# micro_schematic.net
KiCad netlist of a schematic drawn in Altium Designer
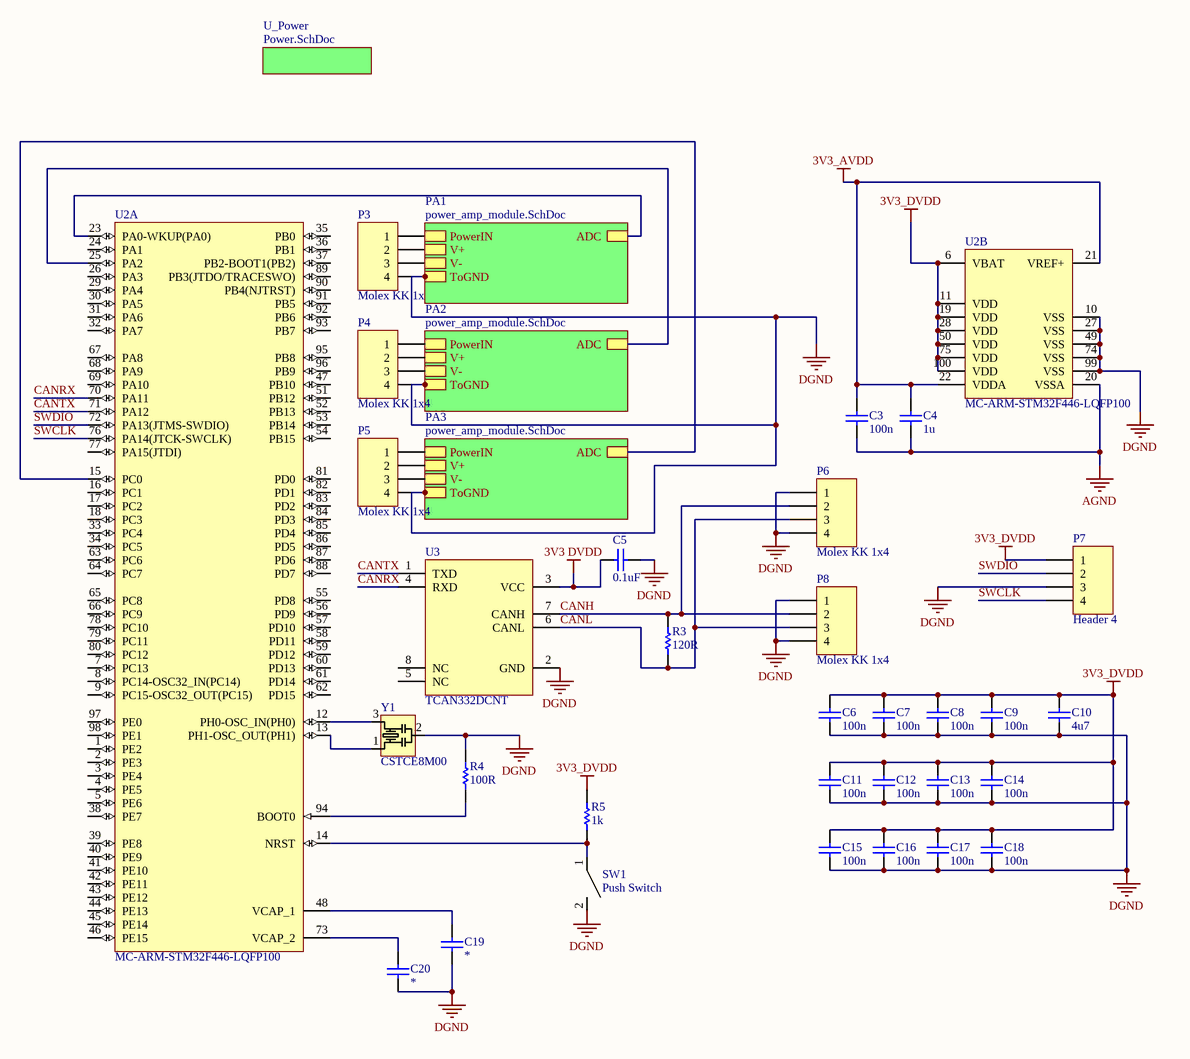
[diagram p0: micro_schematic.SchDoc]

(export (version "E")
  (design (tool "Eeschema 10.0.6"))
  (components
    (comp (ref "C3")
      (value "100n")
      (footprint "C0805")
      (description "0805 Capacitor")
      (libsource (lib "PARSEC") (part "C0805"))
    )
    (comp (ref "C4")
      (value "1u")
      (footprint "C0805")
      (description "0805 Capacitor")
      (libsource (lib "PARSEC") (part "C0805"))
    )
    (comp (ref "C5")
      (value "0.1uF")
      (footprint "C0805")
      (description "0805 Capacitor")
      (libsource (lib "PARSEC") (part "C0805"))
    )
    (comp (ref "C6")
      (value "100n")
      (footprint "C0805")
      (description "0805 Capacitor")
      (libsource (lib "PARSEC") (part "C0805"))
    )
    (comp (ref "C7")
      (value "100n")
      (footprint "C0805")
      (description "0805 Capacitor")
      (libsource (lib "PARSEC") (part "C0805"))
    )
    (comp (ref "C8")
      (value "100n")
      (footprint "C0805")
      (description "0805 Capacitor")
      (libsource (lib "PARSEC") (part "C0805"))
    )
    (comp (ref "C9")
      (value "100n")
      (footprint "C0805")
      (description "0805 Capacitor")
      (libsource (lib "PARSEC") (part "C0805"))
    )
    (comp (ref "C10")
      (value "4u7")
      (footprint "C0805")
      (description "0805 Capacitor")
      (libsource (lib "PARSEC") (part "C0805"))
    )
    (comp (ref "C11")
      (value "100n")
      (footprint "C0805")
      (description "0805 Capacitor")
      (libsource (lib "PARSEC") (part "C0805"))
    )
    (comp (ref "C12")
      (value "100n")
      (footprint "C0805")
      (description "0805 Capacitor")
      (libsource (lib "PARSEC") (part "C0805"))
    )
    (comp (ref "C13")
      (value "100n")
      (footprint "C0805")
      (description "0805 Capacitor")
      (libsource (lib "PARSEC") (part "C0805"))
    )
    (comp (ref "C14")
      (value "100n")
      (footprint "C0805")
      (description "0805 Capacitor")
      (libsource (lib "PARSEC") (part "C0805"))
    )
    (comp (ref "C15")
      (value "100n")
      (footprint "C0805")
      (description "0805 Capacitor")
      (libsource (lib "PARSEC") (part "C0805"))
    )
    (comp (ref "C16")
      (value "100n")
      (footprint "C0805")
      (description "0805 Capacitor")
      (libsource (lib "PARSEC") (part "C0805"))
    )
    (comp (ref "C17")
      (value "100n")
      (footprint "C0805")
      (description "0805 Capacitor")
      (libsource (lib "PARSEC") (part "C0805"))
    )
    (comp (ref "C18")
      (value "100n")
      (footprint "C0805")
      (description "0805 Capacitor")
      (libsource (lib "PARSEC") (part "C0805"))
    )
    (comp (ref "C19")
      (value "*")
      (footprint "C0805")
      (description "0805 Capacitor")
      (fields (field (name "ALTIUM_VALUE") "*"))
      (libsource (lib "PARSEC") (part "C0805"))
    )
    (comp (ref "C20")
      (value "*")
      (footprint "C0805")
      (description "0805 Capacitor")
      (fields (field (name "ALTIUM_VALUE") "*"))
      (libsource (lib "PARSEC") (part "C0805"))
    )
    (comp (ref "P3")
      (value "Molex KK 1x4")
      (footprint "Molex KK 4x1")
      (description "1x4 Molex KK Connector")
      (libsource (lib "") (part "Molex KK 1x4_1"))
    )
    (comp (ref "P4")
      (value "Molex KK 1x4")
      (footprint "Molex KK 4x1")
      (description "1x4 Molex KK Connector")
      (libsource (lib "") (part "Molex KK 1x4_1"))
    )
    (comp (ref "P5")
      (value "Molex KK 1x4")
      (footprint "Molex KK 4x1")
      (description "1x4 Molex KK Connector")
      (libsource (lib "") (part "Molex KK 1x4_1"))
    )
    (comp (ref "P6")
      (value "Molex KK 1x4")
      (footprint "Molex KK 4x1")
      (description "1x4 Molex KK Connector")
      (libsource (lib "PARSEC") (part "Molex KK 1x4"))
    )
    (comp (ref "P7")
      (value "Header 4")
      (footprint "HDR1X4")
      (description "Header, 4-Pin")
      (fields (field (name "PUBLISHER") "Altium Limited"))
      (libsource (lib "Miscellaneous Connectors") (part "Header 4"))
    )
    (comp (ref "P8")
      (value "Molex KK 1x4")
      (footprint "Molex KK 4x1")
      (description "1x4 Molex KK Connector")
      (libsource (lib "PARSEC") (part "Molex KK 1x4"))
    )
    (comp (ref "R3")
      (value "120R")
      (footprint "R0805")
      (description "RESISTOR 0805")
      (libsource (lib "PARSEC") (part "R0805"))
    )
    (comp (ref "R4")
      (value "100R")
      (footprint "R0805")
      (description "RESISTOR 0805")
      (libsource (lib "PARSEC") (part "R0805"))
    )
    (comp (ref "R5")
      (value "1k")
      (footprint "R0805")
      (description "RESISTOR 0805")
      (libsource (lib "PARSEC") (part "R0805"))
    )
    (comp (ref "SW1")
      (value "Push Switch")
      (footprint "PUSHBUTTON")
      (libsource (lib "PARSEC") (part "PUSHBUTTON"))
    )
    (comp (ref "U2")
      (value "MC-ARM-STM32F446-LQFP100")
      (footprint "STM-LQFP100_N")
      (libsource (lib "PARSEC") (part "MC-ARM-STM32F446-LQFP100"))
    )
    (comp (ref "U3")
      (value "TCAN332DCNT")
      (footprint "SOT-23-8")
      (description "IC TXRX CAN 3.3V SOT23-8")
      (libsource (lib "PARSEC") (part "TCAN332DCNT"))
    )
    (comp (ref "Y1")
      (value "CSTCE8M00")
      (footprint "8MHz Ceramic Resonator")
      (description "8MHz Ceramic Resonator")
      (libsource (lib "PARSEC") (part "CSTCE8M00"))
    )
  )
  (nets
    (net (code "1") (name "/ADC") (class "Default")
      (node (ref "U2") (pin "23") (pinfunction "PA0-WKUP(PA0)_23") (pintype "bidirectional"))
    )
    (net (code "2") (name "/ADC_1") (class "Default")
      (node (ref "U2") (pin "15") (pinfunction "PC0_15") (pintype "bidirectional"))
    )
    (net (code "3") (name "/ADC_2") (class "Default")
      (node (ref "U2") (pin "25") (pinfunction "PA2_25") (pintype "bidirectional"))
    )
    (net (code "4") (name "/CANH") (class "Default")
      (node (ref "P6") (pin "2") (pinfunction "2_2") (pintype "passive"))
      (node (ref "P8") (pin "2") (pinfunction "2_2") (pintype "passive"))
      (node (ref "R3") (pin "2") (pinfunction "2_2") (pintype "passive"))
      (node (ref "U3") (pin "7") (pinfunction "CANH_7") (pintype "passive"))
    )
    (net (code "5") (name "/CANL") (class "Default")
      (node (ref "P6") (pin "3") (pinfunction "3_3") (pintype "passive"))
      (node (ref "P8") (pin "3") (pinfunction "3_3") (pintype "passive"))
      (node (ref "R3") (pin "1") (pinfunction "1_1") (pintype "passive"))
      (node (ref "U3") (pin "6") (pinfunction "CANL_6") (pintype "passive"))
    )
    (net (code "6") (name "/CANRX") (class "Default")
      (node (ref "U2") (pin "70") (pinfunction "PA11_70") (pintype "bidirectional"))
      (node (ref "U3") (pin "4") (pinfunction "RXD_4") (pintype "passive"))
    )
    (net (code "7") (name "/CANTX") (class "Default")
      (node (ref "U2") (pin "71") (pinfunction "PA12_71") (pintype "bidirectional"))
      (node (ref "U3") (pin "1") (pinfunction "TXD_1") (pintype "passive"))
    )
    (net (code "8") (name "/PowerIN") (class "Default")
      (node (ref "P5") (pin "1") (pinfunction "1_1") (pintype "passive"))
    )
    (net (code "9") (name "/PowerIN_1") (class "Default")
      (node (ref "P3") (pin "1") (pinfunction "1_1") (pintype "passive"))
    )
    (net (code "10") (name "/PowerIN_2") (class "Default")
      (node (ref "P4") (pin "1") (pinfunction "1_1") (pintype "passive"))
    )
    (net (code "11") (name "/SWCLK") (class "Default")
      (node (ref "P7") (pin "4") (pinfunction "4_4") (pintype "passive"))
      (node (ref "U2") (pin "76") (pinfunction "PA14(JTCK-SWCLK)_76") (pintype "bidirectional"))
    )
    (net (code "12") (name "/SWDIO") (class "Default")
      (node (ref "P7") (pin "2") (pinfunction "2_2") (pintype "passive"))
      (node (ref "U2") (pin "72") (pinfunction "PA13(JTMS-SWDIO)_72") (pintype "bidirectional"))
    )
    (net (code "13") (name "/V+") (class "Default")
      (node (ref "P5") (pin "2") (pinfunction "2_2") (pintype "passive"))
    )
    (net (code "14") (name "/V+_1") (class "Default")
      (node (ref "P3") (pin "2") (pinfunction "2_2") (pintype "passive"))
    )
    (net (code "15") (name "/V+_2") (class "Default")
      (node (ref "P4") (pin "2") (pinfunction "2_2") (pintype "passive"))
    )
    (net (code "16") (name "/V-") (class "Default")
      (node (ref "P5") (pin "3") (pinfunction "3_3") (pintype "passive"))
    )
    (net (code "17") (name "/V-_1") (class "Default")
      (node (ref "P3") (pin "3") (pinfunction "3_3") (pintype "passive"))
    )
    (net (code "18") (name "/V-_2") (class "Default")
      (node (ref "P4") (pin "3") (pinfunction "3_3") (pintype "passive"))
    )
    (net (code "19") (name "3V3 DVDD") (class "Default")
      (node (ref "C5") (pin "1") (pinfunction "1_1") (pintype "passive"))
      (node (ref "U3") (pin "3") (pinfunction "VCC_3") (pintype "passive"))
    )
    (net (code "20") (name "3V3_AVDD") (class "Default")
      (node (ref "C3") (pin "1") (pinfunction "1_1") (pintype "passive"))
      (node (ref "C4") (pin "1") (pinfunction "1_1") (pintype "passive"))
      (node (ref "U2") (pin "21") (pinfunction "VREF+_21") (pintype "power_in"))
      (node (ref "U2") (pin "22") (pinfunction "VDDA_22") (pintype "power_in"))
    )
    (net (code "21") (name "3V3_DVDD") (class "Default")
      (node (ref "C10") (pin "1") (pinfunction "1_1") (pintype "passive"))
      (node (ref "C11") (pin "1") (pinfunction "1_1") (pintype "passive"))
      (node (ref "C12") (pin "1") (pinfunction "1_1") (pintype "passive"))
      (node (ref "C13") (pin "1") (pinfunction "1_1") (pintype "passive"))
      (node (ref "C14") (pin "1") (pinfunction "1_1") (pintype "passive"))
      (node (ref "C15") (pin "1") (pinfunction "1_1") (pintype "passive"))
      (node (ref "C16") (pin "1") (pinfunction "1_1") (pintype "passive"))
      (node (ref "C17") (pin "1") (pinfunction "1_1") (pintype "passive"))
      (node (ref "C18") (pin "1") (pinfunction "1_1") (pintype "passive"))
      (node (ref "C6") (pin "1") (pinfunction "1_1") (pintype "passive"))
      (node (ref "C7") (pin "1") (pinfunction "1_1") (pintype "passive"))
      (node (ref "C8") (pin "1") (pinfunction "1_1") (pintype "passive"))
      (node (ref "C9") (pin "1") (pinfunction "1_1") (pintype "passive"))
      (node (ref "P7") (pin "1") (pinfunction "1_1") (pintype "passive"))
      (node (ref "R5") (pin "2") (pinfunction "2_2") (pintype "passive"))
      (node (ref "U2") (pin "100") (pinfunction "VDD_100") (pintype "power_in"))
      (node (ref "U2") (pin "11") (pinfunction "VDD_11") (pintype "power_in"))
      (node (ref "U2") (pin "19") (pinfunction "VDD_19") (pintype "power_in"))
      (node (ref "U2") (pin "28") (pinfunction "VDD_28") (pintype "power_in"))
      (node (ref "U2") (pin "50") (pinfunction "VDD_50") (pintype "power_in"))
      (node (ref "U2") (pin "6") (pinfunction "VBAT_6") (pintype "power_in"))
      (node (ref "U2") (pin "75") (pinfunction "VDD_75") (pintype "power_in"))
    )
    (net (code "22") (name "AGND") (class "Default")
      (node (ref "C3") (pin "2") (pinfunction "2_2") (pintype "passive"))
      (node (ref "C4") (pin "2") (pinfunction "2_2") (pintype "passive"))
      (node (ref "U2") (pin "20") (pinfunction "VSSA_20") (pintype "power_in"))
    )
    (net (code "23") (name "DGND") (class "Default")
      (node (ref "C10") (pin "2") (pinfunction "2_2") (pintype "passive"))
      (node (ref "C11") (pin "2") (pinfunction "2_2") (pintype "passive"))
      (node (ref "C12") (pin "2") (pinfunction "2_2") (pintype "passive"))
      (node (ref "C13") (pin "2") (pinfunction "2_2") (pintype "passive"))
      (node (ref "C14") (pin "2") (pinfunction "2_2") (pintype "passive"))
      (node (ref "C15") (pin "2") (pinfunction "2_2") (pintype "passive"))
      (node (ref "C16") (pin "2") (pinfunction "2_2") (pintype "passive"))
      (node (ref "C17") (pin "2") (pinfunction "2_2") (pintype "passive"))
      (node (ref "C18") (pin "2") (pinfunction "2_2") (pintype "passive"))
      (node (ref "C19") (pin "2") (pinfunction "2_2") (pintype "passive"))
      (node (ref "C20") (pin "2") (pinfunction "2_2") (pintype "passive"))
      (node (ref "C5") (pin "2") (pinfunction "2_2") (pintype "passive"))
      (node (ref "C6") (pin "2") (pinfunction "2_2") (pintype "passive"))
      (node (ref "C7") (pin "2") (pinfunction "2_2") (pintype "passive"))
      (node (ref "C8") (pin "2") (pinfunction "2_2") (pintype "passive"))
      (node (ref "C9") (pin "2") (pinfunction "2_2") (pintype "passive"))
      (node (ref "P3") (pin "4") (pinfunction "4_4") (pintype "passive"))
      (node (ref "P4") (pin "4") (pinfunction "4_4") (pintype "passive"))
      (node (ref "P5") (pin "4") (pinfunction "4_4") (pintype "passive"))
      (node (ref "P6") (pin "1") (pinfunction "1_1") (pintype "passive"))
      (node (ref "P6") (pin "4") (pinfunction "4_4") (pintype "passive"))
      (node (ref "P7") (pin "3") (pinfunction "3_3") (pintype "passive"))
      (node (ref "P8") (pin "1") (pinfunction "1_1") (pintype "passive"))
      (node (ref "P8") (pin "4") (pinfunction "4_4") (pintype "passive"))
      (node (ref "R4") (pin "2") (pinfunction "2_2") (pintype "passive"))
      (node (ref "SW1") (pin "2") (pinfunction "6_2") (pintype "passive"))
      (node (ref "U2") (pin "10") (pinfunction "VSS_10") (pintype "power_in"))
      (node (ref "U2") (pin "27") (pinfunction "VSS_27") (pintype "power_in"))
      (node (ref "U2") (pin "49") (pinfunction "VSS_49") (pintype "power_in"))
      (node (ref "U2") (pin "74") (pinfunction "VSS_74") (pintype "power_in"))
      (node (ref "U2") (pin "99") (pinfunction "VSS_99") (pintype "power_in"))
      (node (ref "U3") (pin "2") (pinfunction "GND_2") (pintype "passive"))
      (node (ref "Y1") (pin "2") (pinfunction "GND_2") (pintype "passive"))
    )
    (net (code "24") (name "Net-(U2A-BOOT0)") (class "Default")
      (node (ref "R4") (pin "1") (pinfunction "1_1") (pintype "passive"))
      (node (ref "U2") (pin "94") (pinfunction "BOOT0_94") (pintype "input"))
    )
    (net (code "25") (name "Net-(U2A-NRST)") (class "Default")
      (node (ref "R5") (pin "1") (pinfunction "1_1") (pintype "passive"))
      (node (ref "SW1") (pin "1") (pinfunction "1_1") (pintype "passive"))
      (node (ref "U2") (pin "14") (pinfunction "NRST_14") (pintype "bidirectional"))
    )
    (net (code "26") (name "Net-(U2A-PH0-OSC_IN(PH0))") (class "Default")
      (node (ref "U2") (pin "12") (pinfunction "PH0-OSC_IN(PH0)_12") (pintype "bidirectional"))
      (node (ref "Y1") (pin "3") (pinfunction "OSC2_3") (pintype "passive"))
    )
    (net (code "27") (name "Net-(U2A-PH1-OSC_OUT(PH1))") (class "Default")
      (node (ref "U2") (pin "13") (pinfunction "PH1-OSC_OUT(PH1)_13") (pintype "bidirectional"))
      (node (ref "Y1") (pin "1") (pinfunction "OSC1_1") (pintype "passive"))
    )
    (net (code "28") (name "Net-(U2A-VCAP_1)") (class "Default")
      (node (ref "C19") (pin "1") (pinfunction "1_1") (pintype "passive"))
      (node (ref "U2") (pin "48") (pinfunction "VCAP_1_48") (pintype "passive"))
    )
    (net (code "29") (name "Net-(U2A-VCAP_2)") (class "Default")
      (node (ref "C20") (pin "1") (pinfunction "1_1") (pintype "passive"))
      (node (ref "U2") (pin "73") (pinfunction "VCAP_2_73") (pintype "passive"))
    )
    (net (code "30") (name "unconnected-(U2A-PA1-Pad24)") (class "Default")
      (node (ref "U2") (pin "24") (pinfunction "PA1_24") (pintype "bidirectional"))
    )
    (net (code "31") (name "unconnected-(U2A-PA3-Pad26)") (class "Default")
      (node (ref "U2") (pin "26") (pinfunction "PA3_26") (pintype "bidirectional"))
    )
    (net (code "32") (name "unconnected-(U2A-PA4-Pad29)") (class "Default")
      (node (ref "U2") (pin "29") (pinfunction "PA4_29") (pintype "bidirectional"))
    )
    (net (code "33") (name "unconnected-(U2A-PA5-Pad30)") (class "Default")
      (node (ref "U2") (pin "30") (pinfunction "PA5_30") (pintype "bidirectional"))
    )
    (net (code "34") (name "unconnected-(U2A-PA6-Pad31)") (class "Default")
      (node (ref "U2") (pin "31") (pinfunction "PA6_31") (pintype "bidirectional"))
    )
    (net (code "35") (name "unconnected-(U2A-PA7-Pad32)") (class "Default")
      (node (ref "U2") (pin "32") (pinfunction "PA7_32") (pintype "bidirectional"))
    )
    (net (code "36") (name "unconnected-(U2A-PA8-Pad67)") (class "Default")
      (node (ref "U2") (pin "67") (pinfunction "PA8_67") (pintype "bidirectional"))
    )
    (net (code "37") (name "unconnected-(U2A-PA9-Pad68)") (class "Default")
      (node (ref "U2") (pin "68") (pinfunction "PA9_68") (pintype "bidirectional"))
    )
    (net (code "38") (name "unconnected-(U2A-PA10-Pad69)") (class "Default")
      (node (ref "U2") (pin "69") (pinfunction "PA10_69") (pintype "bidirectional"))
    )
    (net (code "39") (name "unconnected-(U2A-PA15(JTDI)-Pad77)") (class "Default")
      (node (ref "U2") (pin "77") (pinfunction "PA15(JTDI)_77") (pintype "bidirectional"))
    )
    (net (code "40") (name "unconnected-(U2A-PB0-Pad35)") (class "Default")
      (node (ref "U2") (pin "35") (pinfunction "PB0_35") (pintype "bidirectional"))
    )
    (net (code "41") (name "unconnected-(U2A-PB1-Pad36)") (class "Default")
      (node (ref "U2") (pin "36") (pinfunction "PB1_36") (pintype "bidirectional"))
    )
    (net (code "42") (name "unconnected-(U2A-PB2-BOOT1(PB2)-Pad37)") (class "Default")
      (node (ref "U2") (pin "37") (pinfunction "PB2-BOOT1(PB2)_37") (pintype "bidirectional"))
    )
    (net (code "43") (name "unconnected-(U2A-PB3(JTDO{slash}TRACESWO)-Pad89)") (class "Default")
      (node (ref "U2") (pin "89") (pinfunction "PB3(JTDO/TRACESWO)_89") (pintype "bidirectional"))
    )
    (net (code "44") (name "unconnected-(U2A-PB4(NJTRST)-Pad90)") (class "Default")
      (node (ref "U2") (pin "90") (pinfunction "PB4(NJTRST)_90") (pintype "bidirectional"))
    )
    (net (code "45") (name "unconnected-(U2A-PB5-Pad91)") (class "Default")
      (node (ref "U2") (pin "91") (pinfunction "PB5_91") (pintype "bidirectional"))
    )
    (net (code "46") (name "unconnected-(U2A-PB6-Pad92)") (class "Default")
      (node (ref "U2") (pin "92") (pinfunction "PB6_92") (pintype "bidirectional"))
    )
    (net (code "47") (name "unconnected-(U2A-PB7-Pad93)") (class "Default")
      (node (ref "U2") (pin "93") (pinfunction "PB7_93") (pintype "bidirectional"))
    )
    (net (code "48") (name "unconnected-(U2A-PB8-Pad95)") (class "Default")
      (node (ref "U2") (pin "95") (pinfunction "PB8_95") (pintype "bidirectional"))
    )
    (net (code "49") (name "unconnected-(U2A-PB9-Pad96)") (class "Default")
      (node (ref "U2") (pin "96") (pinfunction "PB9_96") (pintype "bidirectional"))
    )
    (net (code "50") (name "unconnected-(U2A-PB10-Pad47)") (class "Default")
      (node (ref "U2") (pin "47") (pinfunction "PB10_47") (pintype "bidirectional"))
    )
    (net (code "51") (name "unconnected-(U2A-PB12-Pad51)") (class "Default")
      (node (ref "U2") (pin "51") (pinfunction "PB12_51") (pintype "bidirectional"))
    )
    (net (code "52") (name "unconnected-(U2A-PB13-Pad52)") (class "Default")
      (node (ref "U2") (pin "52") (pinfunction "PB13_52") (pintype "bidirectional"))
    )
    (net (code "53") (name "unconnected-(U2A-PB14-Pad53)") (class "Default")
      (node (ref "U2") (pin "53") (pinfunction "PB14_53") (pintype "bidirectional"))
    )
    (net (code "54") (name "unconnected-(U2A-PB15-Pad54)") (class "Default")
      (node (ref "U2") (pin "54") (pinfunction "PB15_54") (pintype "bidirectional"))
    )
    (net (code "55") (name "unconnected-(U2A-PC1-Pad16)") (class "Default")
      (node (ref "U2") (pin "16") (pinfunction "PC1_16") (pintype "bidirectional"))
    )
    (net (code "56") (name "unconnected-(U2A-PC2-Pad17)") (class "Default")
      (node (ref "U2") (pin "17") (pinfunction "PC2_17") (pintype "bidirectional"))
    )
    (net (code "57") (name "unconnected-(U2A-PC3-Pad18)") (class "Default")
      (node (ref "U2") (pin "18") (pinfunction "PC3_18") (pintype "bidirectional"))
    )
    (net (code "58") (name "unconnected-(U2A-PC4-Pad33)") (class "Default")
      (node (ref "U2") (pin "33") (pinfunction "PC4_33") (pintype "bidirectional"))
    )
    (net (code "59") (name "unconnected-(U2A-PC5-Pad34)") (class "Default")
      (node (ref "U2") (pin "34") (pinfunction "PC5_34") (pintype "bidirectional"))
    )
    (net (code "60") (name "unconnected-(U2A-PC6-Pad63)") (class "Default")
      (node (ref "U2") (pin "63") (pinfunction "PC6_63") (pintype "bidirectional"))
    )
    (net (code "61") (name "unconnected-(U2A-PC7-Pad64)") (class "Default")
      (node (ref "U2") (pin "64") (pinfunction "PC7_64") (pintype "bidirectional"))
    )
    (net (code "62") (name "unconnected-(U2A-PC8-Pad65)") (class "Default")
      (node (ref "U2") (pin "65") (pinfunction "PC8_65") (pintype "bidirectional"))
    )
    (net (code "63") (name "unconnected-(U2A-PC9-Pad66)") (class "Default")
      (node (ref "U2") (pin "66") (pinfunction "PC9_66") (pintype "bidirectional"))
    )
    (net (code "64") (name "unconnected-(U2A-PC10-Pad78)") (class "Default")
      (node (ref "U2") (pin "78") (pinfunction "PC10_78") (pintype "bidirectional"))
    )
    (net (code "65") (name "unconnected-(U2A-PC11-Pad79)") (class "Default")
      (node (ref "U2") (pin "79") (pinfunction "PC11_79") (pintype "bidirectional"))
    )
    (net (code "66") (name "unconnected-(U2A-PC12-Pad80)") (class "Default")
      (node (ref "U2") (pin "80") (pinfunction "PC12_80") (pintype "bidirectional"))
    )
    (net (code "67") (name "unconnected-(U2A-PC13-Pad7)") (class "Default")
      (node (ref "U2") (pin "7") (pinfunction "PC13_7") (pintype "bidirectional"))
    )
    (net (code "68") (name "unconnected-(U2A-PC14-OSC32_IN(PC14)-Pad8)") (class "Default")
      (node (ref "U2") (pin "8") (pinfunction "PC14-OSC32_IN(PC14)_8") (pintype "bidirectional"))
    )
    (net (code "69") (name "unconnected-(U2A-PC15-OSC32_OUT(PC15)-Pad9)") (class "Default")
      (node (ref "U2") (pin "9") (pinfunction "PC15-OSC32_OUT(PC15)_9") (pintype "bidirectional"))
    )
    (net (code "70") (name "unconnected-(U2A-PD0-Pad81)") (class "Default")
      (node (ref "U2") (pin "81") (pinfunction "PD0_81") (pintype "bidirectional"))
    )
    (net (code "71") (name "unconnected-(U2A-PD1-Pad82)") (class "Default")
      (node (ref "U2") (pin "82") (pinfunction "PD1_82") (pintype "bidirectional"))
    )
    (net (code "72") (name "unconnected-(U2A-PD2-Pad83)") (class "Default")
      (node (ref "U2") (pin "83") (pinfunction "PD2_83") (pintype "bidirectional"))
    )
    (net (code "73") (name "unconnected-(U2A-PD3-Pad84)") (class "Default")
      (node (ref "U2") (pin "84") (pinfunction "PD3_84") (pintype "bidirectional"))
    )
    (net (code "74") (name "unconnected-(U2A-PD4-Pad85)") (class "Default")
      (node (ref "U2") (pin "85") (pinfunction "PD4_85") (pintype "bidirectional"))
    )
    (net (code "75") (name "unconnected-(U2A-PD5-Pad86)") (class "Default")
      (node (ref "U2") (pin "86") (pinfunction "PD5_86") (pintype "bidirectional"))
    )
    (net (code "76") (name "unconnected-(U2A-PD6-Pad87)") (class "Default")
      (node (ref "U2") (pin "87") (pinfunction "PD6_87") (pintype "bidirectional"))
    )
    (net (code "77") (name "unconnected-(U2A-PD7-Pad88)") (class "Default")
      (node (ref "U2") (pin "88") (pinfunction "PD7_88") (pintype "bidirectional"))
    )
    (net (code "78") (name "unconnected-(U2A-PD8-Pad55)") (class "Default")
      (node (ref "U2") (pin "55") (pinfunction "PD8_55") (pintype "bidirectional"))
    )
    (net (code "79") (name "unconnected-(U2A-PD9-Pad56)") (class "Default")
      (node (ref "U2") (pin "56") (pinfunction "PD9_56") (pintype "bidirectional"))
    )
    (net (code "80") (name "unconnected-(U2A-PD10-Pad57)") (class "Default")
      (node (ref "U2") (pin "57") (pinfunction "PD10_57") (pintype "bidirectional"))
    )
    (net (code "81") (name "unconnected-(U2A-PD11-Pad58)") (class "Default")
      (node (ref "U2") (pin "58") (pinfunction "PD11_58") (pintype "bidirectional"))
    )
    (net (code "82") (name "unconnected-(U2A-PD12-Pad59)") (class "Default")
      (node (ref "U2") (pin "59") (pinfunction "PD12_59") (pintype "bidirectional"))
    )
    (net (code "83") (name "unconnected-(U2A-PD13-Pad60)") (class "Default")
      (node (ref "U2") (pin "60") (pinfunction "PD13_60") (pintype "bidirectional"))
    )
    (net (code "84") (name "unconnected-(U2A-PD14-Pad61)") (class "Default")
      (node (ref "U2") (pin "61") (pinfunction "PD14_61") (pintype "bidirectional"))
    )
    (net (code "85") (name "unconnected-(U2A-PD15-Pad62)") (class "Default")
      (node (ref "U2") (pin "62") (pinfunction "PD15_62") (pintype "bidirectional"))
    )
    (net (code "86") (name "unconnected-(U2A-PE0-Pad97)") (class "Default")
      (node (ref "U2") (pin "97") (pinfunction "PE0_97") (pintype "bidirectional"))
    )
    (net (code "87") (name "unconnected-(U2A-PE1-Pad98)") (class "Default")
      (node (ref "U2") (pin "98") (pinfunction "PE1_98") (pintype "bidirectional"))
    )
    (net (code "88") (name "unconnected-(U2A-PE2-Pad1)") (class "Default")
      (node (ref "U2") (pin "1") (pinfunction "PE2_1") (pintype "bidirectional"))
    )
    (net (code "89") (name "unconnected-(U2A-PE3-Pad2)") (class "Default")
      (node (ref "U2") (pin "2") (pinfunction "PE3_2") (pintype "bidirectional"))
    )
    (net (code "90") (name "unconnected-(U2A-PE4-Pad3)") (class "Default")
      (node (ref "U2") (pin "3") (pinfunction "PE4_3") (pintype "bidirectional"))
    )
    (net (code "91") (name "unconnected-(U2A-PE5-Pad4)") (class "Default")
      (node (ref "U2") (pin "4") (pinfunction "PE5_4") (pintype "bidirectional"))
    )
    (net (code "92") (name "unconnected-(U2A-PE6-Pad5)") (class "Default")
      (node (ref "U2") (pin "5") (pinfunction "PE6_5") (pintype "bidirectional"))
    )
    (net (code "93") (name "unconnected-(U2A-PE7-Pad38)") (class "Default")
      (node (ref "U2") (pin "38") (pinfunction "PE7_38") (pintype "bidirectional"))
    )
    (net (code "94") (name "unconnected-(U2A-PE8-Pad39)") (class "Default")
      (node (ref "U2") (pin "39") (pinfunction "PE8_39") (pintype "bidirectional"))
    )
    (net (code "95") (name "unconnected-(U2A-PE9-Pad40)") (class "Default")
      (node (ref "U2") (pin "40") (pinfunction "PE9_40") (pintype "bidirectional"))
    )
    (net (code "96") (name "unconnected-(U2A-PE10-Pad41)") (class "Default")
      (node (ref "U2") (pin "41") (pinfunction "PE10_41") (pintype "bidirectional"))
    )
    (net (code "97") (name "unconnected-(U2A-PE11-Pad42)") (class "Default")
      (node (ref "U2") (pin "42") (pinfunction "PE11_42") (pintype "bidirectional"))
    )
    (net (code "98") (name "unconnected-(U2A-PE12-Pad43)") (class "Default")
      (node (ref "U2") (pin "43") (pinfunction "PE12_43") (pintype "bidirectional"))
    )
    (net (code "99") (name "unconnected-(U2A-PE13-Pad44)") (class "Default")
      (node (ref "U2") (pin "44") (pinfunction "PE13_44") (pintype "bidirectional"))
    )
    (net (code "100") (name "unconnected-(U2A-PE14-Pad45)") (class "Default")
      (node (ref "U2") (pin "45") (pinfunction "PE14_45") (pintype "bidirectional"))
    )
    (net (code "101") (name "unconnected-(U2A-PE15-Pad46)") (class "Default")
      (node (ref "U2") (pin "46") (pinfunction "PE15_46") (pintype "bidirectional"))
    )
    (net (code "102") (name "unconnected-(U3-NC-Pad5)") (class "Default")
      (node (ref "U3") (pin "5") (pinfunction "NC_5") (pintype "passive"))
    )
    (net (code "103") (name "unconnected-(U3-NC-Pad8)") (class "Default")
      (node (ref "U3") (pin "8") (pinfunction "NC_8") (pintype "passive"))
    )
  )
)
